# boot_kurz.net
KiCad netlist of a schematic drawn in EAGLE
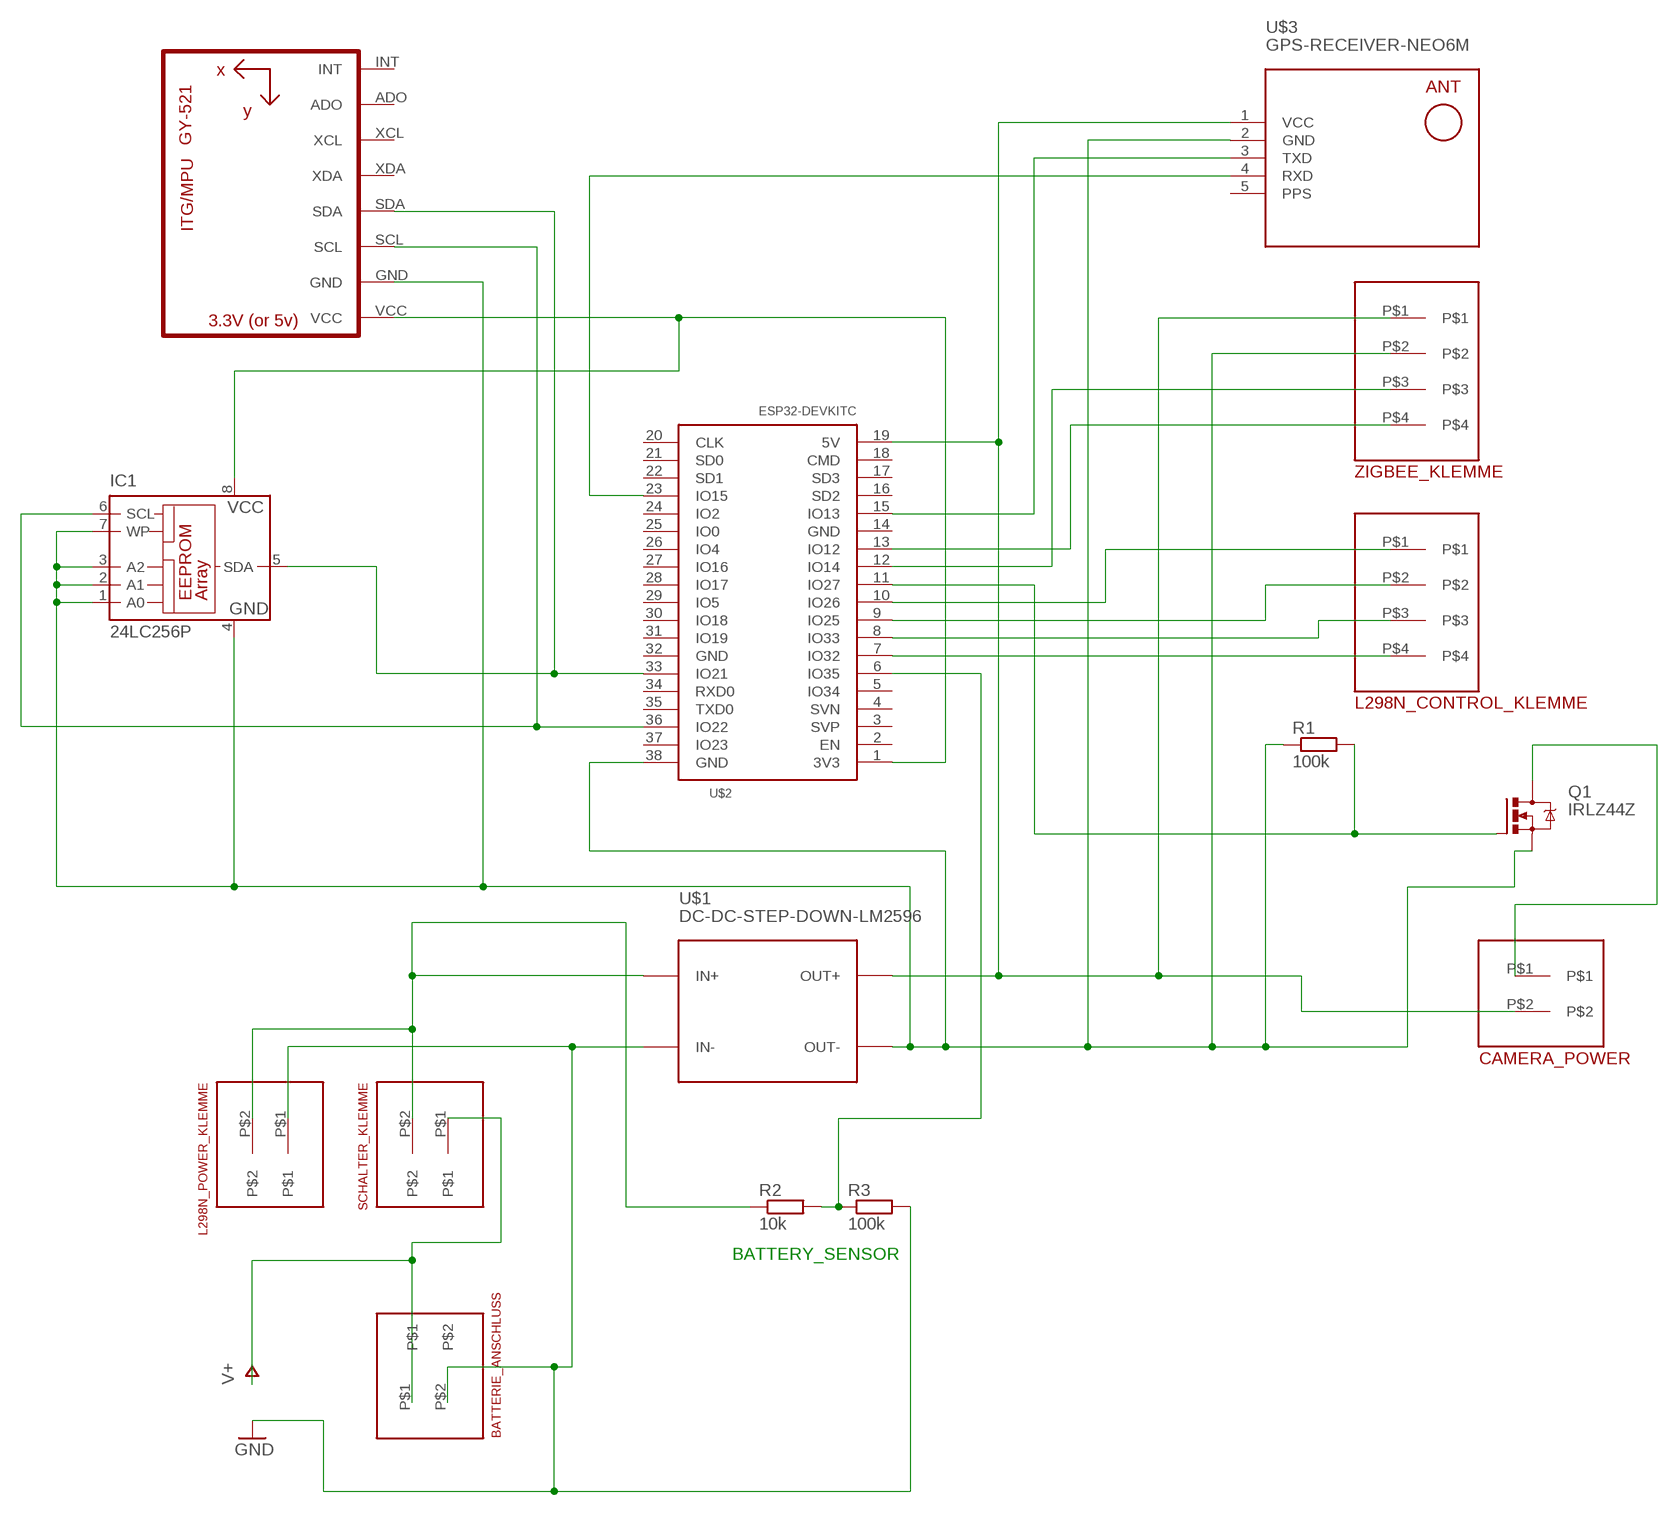
[diagram p0: schematic, sheet 1]

(export (version "E")
  (design (tool "Eeschema 10.0.6"))
  (components
    (comp (ref "BATTERIE_ANSCHLUSS")
      (value "SCHRAUBKLEMME_X_2RM5.08")
      (footprint "eagle-import:2_PIN_RM5.08")
      (libsource (lib "eagle-import") (part "SCHRAUBKLEMME_X_2RM5.08"))
    )
    (comp (ref "CAMERA_POWER")
      (value "AKL_349_X2")
      (footprint "eagle-import:2_PIN_AKL_349_BUCHSE")
      (libsource (lib "eagle-import") (part "AKL_349_X2"))
    )
    (comp (ref "IC1")
      (value "24LC256P")
      (footprint "eagle-import:DIL8")
      (fields (field (name "MF") "MICROCHIP") (field (name "MPN") "24LC256-E/P"))
      (libsource (lib "eagle-import") (part "24PLC256"))
    )
    (comp (ref "L298N_CONTROL_KLEMME")
      (value "SCHRAUBKLEMME_X_4")
      (footprint "eagle-import:4_PIN_RM5.08_SCHRAUBKLEMME")
      (libsource (lib "eagle-import") (part "SCHRAUBKLEMME_X_4"))
    )
    (comp (ref "L298N_POWER_KLEMME")
      (value "SCHRAUBKLEMME_X_2RM5.08")
      (footprint "eagle-import:2_PIN_RM5.08")
      (libsource (lib "eagle-import") (part "SCHRAUBKLEMME_X_2RM5.08"))
    )
    (comp (ref "Q1")
      (value "IRLZ44Z")
      (footprint "eagle-import:TO220BH")
      (libsource (lib "eagle-import") (part "IRLZ44Z"))
    )
    (comp (ref "R1")
      (value "100k")
      (footprint "eagle-import:0207_7")
      (libsource (lib "eagle-import") (part "R-EU_0207/7"))
    )
    (comp (ref "R2")
      (value "10k")
      (footprint "eagle-import:0207_7")
      (libsource (lib "eagle-import") (part "R-EU_0207/7"))
    )
    (comp (ref "R3")
      (value "100k")
      (footprint "eagle-import:0207_7")
      (libsource (lib "eagle-import") (part "R-EU_0207/7"))
    )
    (comp (ref "SCHALTER_KLEMME")
      (value "SCHRAUBKLEMME_X_2RM5.08")
      (footprint "eagle-import:2_PIN_RM5.08")
      (libsource (lib "eagle-import") (part "SCHRAUBKLEMME_X_2RM5.08"))
    )
    (comp (ref "U$1")
      (value "DC-DC-STEP-DOWN-LM2596")
      (footprint "eagle-import:DC-DC-STEP-DOWN-LM2596")
      (libsource (lib "eagle-import") (part "DC-DC-STEP-DOWN-LM2596"))
    )
    (comp (ref "U$2")
      (value "ESP32DEVKITC")
      (footprint "eagle-import:ESP32-DEVKITC")
      (libsource (lib "eagle-import") (part "ESP32DEVKITC"))
    )
    (comp (ref "U$3")
      (value "GPS-RECEIVER-NEO6M")
      (footprint "eagle-import:GPS-RECEIVER-NEO6M")
      (libsource (lib "eagle-import") (part "GPS-RECEIVER-NEO6M"))
    )
    (comp (ref "U1")
      (value "GY-521MPU6050")
      (footprint "eagle-import:GY-521")
      (libsource (lib "eagle-import") (part "GY-521MPU6050"))
    )
    (comp (ref "ZIGBEE_KLEMME")
      (value "SCHRAUBKLEMME_X_4")
      (footprint "eagle-import:4_PIN_RM5.08_SCHRAUBKLEMME")
      (libsource (lib "eagle-import") (part "SCHRAUBKLEMME_X_4"))
    )
  )
  (nets
    (net (code "1") (name "/PPS") (class "Default")
      (node (ref "U$3") (pin "5") (pinfunction "PPS_5") (pintype "power_in"))
    )
    (net (code "2") (name "GND") (class "Default")
      (node (ref "BATTERIE_ANSCHLUSS") (pin "P$2") (pinfunction "P$2_P$2") (pintype "bidirectional"))
      (node (ref "L298N_POWER_KLEMME") (pin "P$1") (pinfunction "P$1_P$1") (pintype "bidirectional"))
      (node (ref "R3") (pin "2") (pinfunction "2_2") (pintype "passive"))
      (node (ref "U$1") (pin "IN-") (pinfunction "IN-_IN-") (pintype "bidirectional"))
    )
    (net (code "3") (name "Net-(CAMERA_POWER-PadP$1)") (class "Default")
      (node (ref "CAMERA_POWER") (pin "P$1") (pinfunction "P$1_P$1") (pintype "bidirectional"))
      (node (ref "Q1") (pin "D") (pinfunction "D_D") (pintype "passive"))
    )
    (net (code "4") (name "Net-(IC1-A0)") (class "Default")
      (node (ref "IC1") (pin "1") (pinfunction "A0_1") (pintype "input"))
      (node (ref "IC1") (pin "2") (pinfunction "A1_2") (pintype "input"))
      (node (ref "IC1") (pin "3") (pinfunction "A2_3") (pintype "input"))
      (node (ref "IC1") (pin "4") (pinfunction "GND_4") (pintype "power_in"))
      (node (ref "IC1") (pin "7") (pinfunction "WP_7") (pintype "input"))
      (node (ref "Q1") (pin "S") (pinfunction "S_S") (pintype "passive"))
      (node (ref "R1") (pin "1") (pinfunction "1_1") (pintype "passive"))
      (node (ref "U$1") (pin "OUT-") (pinfunction "OUT-_OUT-") (pintype "bidirectional"))
      (node (ref "U$2") (pin "38") (pinfunction "GND_38") (pintype "bidirectional"))
      (node (ref "U$3") (pin "2") (pinfunction "GND_2") (pintype "bidirectional"))
      (node (ref "U1") (pin "GND") (pinfunction "GND_GND") (pintype "bidirectional"))
      (node (ref "ZIGBEE_KLEMME") (pin "P$2") (pinfunction "P$2_P$2") (pintype "bidirectional"))
    )
    (net (code "5") (name "Net-(IC1-SCL)") (class "Default")
      (node (ref "IC1") (pin "6") (pinfunction "SCL_6") (pintype "input"))
      (node (ref "U$2") (pin "36") (pinfunction "IO22_36") (pintype "bidirectional"))
      (node (ref "U1") (pin "SCL") (pinfunction "SCL_SCL") (pintype "bidirectional"))
    )
    (net (code "6") (name "Net-(IC1-SDA)") (class "Default")
      (node (ref "IC1") (pin "5") (pinfunction "SDA_5") (pintype "bidirectional"))
      (node (ref "U$2") (pin "33") (pinfunction "IO21_33") (pintype "bidirectional"))
      (node (ref "U1") (pin "SDA") (pinfunction "SDA_SDA") (pintype "bidirectional"))
    )
    (net (code "7") (name "Net-(IC1-VCC)") (class "Default")
      (node (ref "IC1") (pin "8") (pinfunction "VCC_8") (pintype "power_in"))
      (node (ref "U$2") (pin "1") (pinfunction "3V3_1") (pintype "bidirectional"))
      (node (ref "U1") (pin "VCC") (pinfunction "VCC_VCC") (pintype "bidirectional"))
    )
    (net (code "8") (name "Net-(L298N_POWER_KLEMME-PadP$2)") (class "Default")
      (node (ref "L298N_POWER_KLEMME") (pin "P$2") (pinfunction "P$2_P$2") (pintype "bidirectional"))
      (node (ref "R2") (pin "1") (pinfunction "1_1") (pintype "passive"))
      (node (ref "SCHALTER_KLEMME") (pin "P$2") (pinfunction "P$2_P$2") (pintype "bidirectional"))
      (node (ref "U$1") (pin "IN+") (pinfunction "IN+_IN+") (pintype "bidirectional"))
    )
    (net (code "9") (name "Net-(U$2-5V)") (class "Default")
      (node (ref "CAMERA_POWER") (pin "P$2") (pinfunction "P$2_P$2") (pintype "bidirectional"))
      (node (ref "U$1") (pin "OUT+") (pinfunction "OUT+_OUT+") (pintype "bidirectional"))
      (node (ref "U$2") (pin "19") (pinfunction "5V_19") (pintype "bidirectional"))
      (node (ref "U$3") (pin "1") (pinfunction "VCC_1") (pintype "bidirectional"))
      (node (ref "ZIGBEE_KLEMME") (pin "P$1") (pinfunction "P$1_P$1") (pintype "bidirectional"))
    )
    (net (code "10") (name "Net-(U$2-IO12)") (class "Default")
      (node (ref "U$2") (pin "13") (pinfunction "IO12_13") (pintype "bidirectional"))
      (node (ref "ZIGBEE_KLEMME") (pin "P$4") (pinfunction "P$4_P$4") (pintype "bidirectional"))
    )
    (net (code "11") (name "Net-(U$2-IO13)") (class "Default")
      (node (ref "U$2") (pin "15") (pinfunction "IO13_15") (pintype "bidirectional"))
      (node (ref "U$3") (pin "3") (pinfunction "TXD_3") (pintype "bidirectional"))
    )
    (net (code "12") (name "Net-(U$2-IO14)") (class "Default")
      (node (ref "U$2") (pin "12") (pinfunction "IO14_12") (pintype "bidirectional"))
      (node (ref "ZIGBEE_KLEMME") (pin "P$3") (pinfunction "P$3_P$3") (pintype "bidirectional"))
    )
    (net (code "13") (name "Net-(U$2-IO15)") (class "Default")
      (node (ref "U$2") (pin "23") (pinfunction "IO15_23") (pintype "bidirectional"))
      (node (ref "U$3") (pin "4") (pinfunction "RXD_4") (pintype "power_in"))
    )
    (net (code "14") (name "Net-(U$2-IO25)") (class "Default")
      (node (ref "L298N_CONTROL_KLEMME") (pin "P$2") (pinfunction "P$2_P$2") (pintype "bidirectional"))
      (node (ref "U$2") (pin "9") (pinfunction "IO25_9") (pintype "bidirectional"))
    )
    (net (code "15") (name "Net-(U$2-IO26)") (class "Default")
      (node (ref "L298N_CONTROL_KLEMME") (pin "P$1") (pinfunction "P$1_P$1") (pintype "bidirectional"))
      (node (ref "U$2") (pin "10") (pinfunction "IO26_10") (pintype "bidirectional"))
    )
    (net (code "16") (name "Net-(U$2-IO27)") (class "Default")
      (node (ref "Q1") (pin "G") (pinfunction "G_G") (pintype "passive"))
      (node (ref "R1") (pin "2") (pinfunction "2_2") (pintype "passive"))
      (node (ref "U$2") (pin "11") (pinfunction "IO27_11") (pintype "bidirectional"))
    )
    (net (code "17") (name "Net-(U$2-IO32)") (class "Default")
      (node (ref "L298N_CONTROL_KLEMME") (pin "P$4") (pinfunction "P$4_P$4") (pintype "bidirectional"))
      (node (ref "U$2") (pin "7") (pinfunction "IO32_7") (pintype "bidirectional"))
    )
    (net (code "18") (name "Net-(U$2-IO33)") (class "Default")
      (node (ref "L298N_CONTROL_KLEMME") (pin "P$3") (pinfunction "P$3_P$3") (pintype "bidirectional"))
      (node (ref "U$2") (pin "8") (pinfunction "IO33_8") (pintype "bidirectional"))
    )
    (net (code "19") (name "Net-(U$2-IO35)") (class "Default")
      (node (ref "R2") (pin "2") (pinfunction "2_2") (pintype "passive"))
      (node (ref "R3") (pin "1") (pinfunction "1_1") (pintype "passive"))
      (node (ref "U$2") (pin "6") (pinfunction "IO35_6") (pintype "bidirectional"))
    )
    (net (code "20") (name "V+") (class "Default")
      (node (ref "BATTERIE_ANSCHLUSS") (pin "P$1") (pinfunction "P$1_P$1") (pintype "bidirectional"))
      (node (ref "SCHALTER_KLEMME") (pin "P$1") (pinfunction "P$1_P$1") (pintype "bidirectional"))
    )
    (net (code "21") (name "unconnected-(U$2-CLK-Pad20)") (class "Default")
      (node (ref "U$2") (pin "20") (pinfunction "CLK_20") (pintype "bidirectional"))
    )
    (net (code "22") (name "unconnected-(U$2-CMD-Pad18)") (class "Default")
      (node (ref "U$2") (pin "18") (pinfunction "CMD_18") (pintype "bidirectional"))
    )
    (net (code "23") (name "unconnected-(U$2-EN-Pad2)") (class "Default")
      (node (ref "U$2") (pin "2") (pinfunction "EN_2") (pintype "bidirectional"))
    )
    (net (code "24") (name "unconnected-(U$2-GND-Pad14)") (class "Default")
      (node (ref "U$2") (pin "14") (pinfunction "GND_14") (pintype "bidirectional"))
    )
    (net (code "25") (name "unconnected-(U$2-GND-Pad32)") (class "Default")
      (node (ref "U$2") (pin "32") (pinfunction "GND_32") (pintype "bidirectional"))
    )
    (net (code "26") (name "unconnected-(U$2-IO0-Pad25)") (class "Default")
      (node (ref "U$2") (pin "25") (pinfunction "IO0_25") (pintype "bidirectional"))
    )
    (net (code "27") (name "unconnected-(U$2-IO2-Pad24)") (class "Default")
      (node (ref "U$2") (pin "24") (pinfunction "IO2_24") (pintype "bidirectional"))
    )
    (net (code "28") (name "unconnected-(U$2-IO4-Pad26)") (class "Default")
      (node (ref "U$2") (pin "26") (pinfunction "IO4_26") (pintype "bidirectional"))
    )
    (net (code "29") (name "unconnected-(U$2-IO5-Pad29)") (class "Default")
      (node (ref "U$2") (pin "29") (pinfunction "IO5_29") (pintype "bidirectional"))
    )
    (net (code "30") (name "unconnected-(U$2-IO16-Pad27)") (class "Default")
      (node (ref "U$2") (pin "27") (pinfunction "IO16_27") (pintype "bidirectional"))
    )
    (net (code "31") (name "unconnected-(U$2-IO17-Pad28)") (class "Default")
      (node (ref "U$2") (pin "28") (pinfunction "IO17_28") (pintype "bidirectional"))
    )
    (net (code "32") (name "unconnected-(U$2-IO18-Pad30)") (class "Default")
      (node (ref "U$2") (pin "30") (pinfunction "IO18_30") (pintype "bidirectional"))
    )
    (net (code "33") (name "unconnected-(U$2-IO19-Pad31)") (class "Default")
      (node (ref "U$2") (pin "31") (pinfunction "IO19_31") (pintype "bidirectional"))
    )
    (net (code "34") (name "unconnected-(U$2-IO23-Pad37)") (class "Default")
      (node (ref "U$2") (pin "37") (pinfunction "IO23_37") (pintype "bidirectional"))
    )
    (net (code "35") (name "unconnected-(U$2-IO34-Pad5)") (class "Default")
      (node (ref "U$2") (pin "5") (pinfunction "IO34_5") (pintype "bidirectional"))
    )
    (net (code "36") (name "unconnected-(U$2-RXD0-Pad34)") (class "Default")
      (node (ref "U$2") (pin "34") (pinfunction "RXD0_34") (pintype "bidirectional"))
    )
    (net (code "37") (name "unconnected-(U$2-SD0-Pad21)") (class "Default")
      (node (ref "U$2") (pin "21") (pinfunction "SD0_21") (pintype "bidirectional"))
    )
    (net (code "38") (name "unconnected-(U$2-SD1-Pad22)") (class "Default")
      (node (ref "U$2") (pin "22") (pinfunction "SD1_22") (pintype "bidirectional"))
    )
    (net (code "39") (name "unconnected-(U$2-SD2-Pad16)") (class "Default")
      (node (ref "U$2") (pin "16") (pinfunction "SD2_16") (pintype "bidirectional"))
    )
    (net (code "40") (name "unconnected-(U$2-SD3-Pad17)") (class "Default")
      (node (ref "U$2") (pin "17") (pinfunction "SD3_17") (pintype "bidirectional"))
    )
    (net (code "41") (name "unconnected-(U$2-SVN-Pad4)") (class "Default")
      (node (ref "U$2") (pin "4") (pinfunction "SVN_4") (pintype "bidirectional"))
    )
    (net (code "42") (name "unconnected-(U$2-SVP-Pad3)") (class "Default")
      (node (ref "U$2") (pin "3") (pinfunction "SVP_3") (pintype "bidirectional"))
    )
    (net (code "43") (name "unconnected-(U$2-TXD0-Pad35)") (class "Default")
      (node (ref "U$2") (pin "35") (pinfunction "TXD0_35") (pintype "bidirectional"))
    )
    (net (code "44") (name "unconnected-(U1-PadADO)") (class "Default")
      (node (ref "U1") (pin "ADO") (pinfunction "ADO_ADO") (pintype "bidirectional"))
    )
    (net (code "45") (name "unconnected-(U1-PadINT)") (class "Default")
      (node (ref "U1") (pin "INT") (pinfunction "INT_INT") (pintype "bidirectional"))
    )
    (net (code "46") (name "unconnected-(U1-PadXCL)") (class "Default")
      (node (ref "U1") (pin "XCL") (pinfunction "XCL_XCL") (pintype "bidirectional"))
    )
    (net (code "47") (name "unconnected-(U1-PadXDA)") (class "Default")
      (node (ref "U1") (pin "XDA") (pinfunction "XDA_XDA") (pintype "bidirectional"))
    )
  )
)
